# bq24259_BatteryCharger.net
KiCad netlist of a schematic drawn in Altium Designer
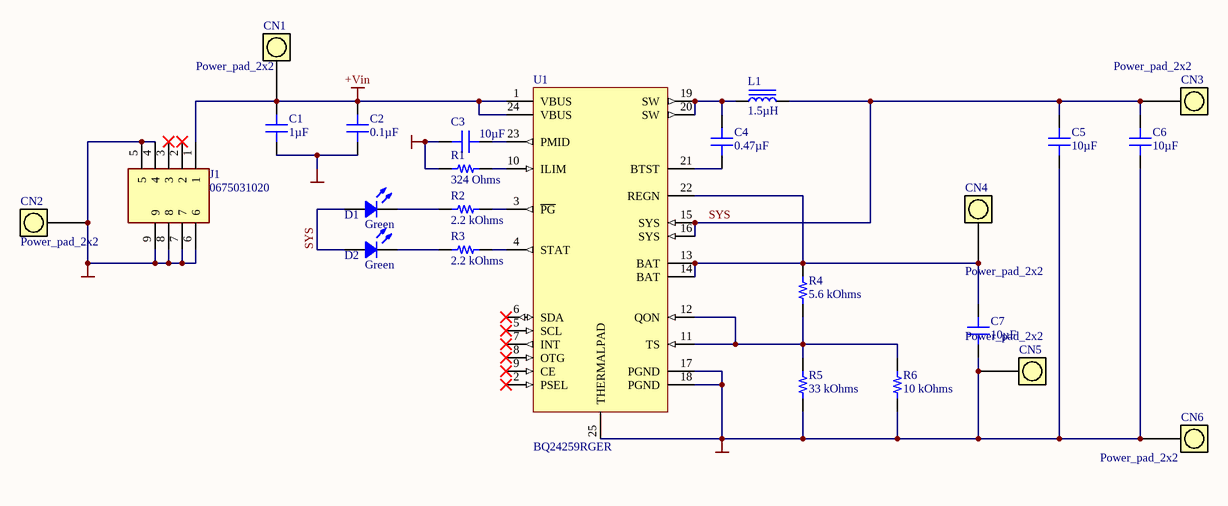
[diagram p0: bq24259_BatteryCharger.SchDoc]

(export (version "E")
  (design (tool "Eeschema 10.0.6"))
  (components
    (comp (ref "C1")
      (value "1µF")
      (footprint "CAP 0805_2012")
      (description "CAP CER 1UF 10V X7R 0805")
      (fields (field (name "PART NUMBER") "MM05ZC105KCZ2A") (field (name "MANUFACTURER") "AVX Corporation"))
      (libsource (lib "Celestial Altium Library - altium_library") (part "Capacitor"))
    )
    (comp (ref "C2")
      (value "0.1µF")
      (footprint "CAP 0805_2012")
      (description "CAP CER 0.1UF 50V X7R 0805")
      (fields (field (name "PART NUMBER") "CC0805MRX7R9BB104") (field (name "MANUFACTURER") "Yageo"))
      (libsource (lib "Celestial Altium Library - altium_library") (part "Capacitor"))
    )
    (comp (ref "C3")
      (value "10µF")
      (footprint "CAP 0805_2012")
      (description "CAP CER 10UF 6.3V X7R 0805")
      (fields (field (name "PART NUMBER") "C0805X106K9RACAUTO") (field (name "MANUFACTURER") "KEMET"))
      (libsource (lib "Celestial Altium Library - altium_library") (part "Capacitor"))
    )
    (comp (ref "C4")
      (value "0.47µF")
      (footprint "CAP 0805_2012")
      (description "CAP CER 0.47UF 50V X7R 0805")
      (fields (field (name "PART NUMBER") "C0805C474K5RACAUTO") (field (name "MANUFACTURER") "KEMET"))
      (libsource (lib "Celestial Altium Library - altium_library") (part "Capacitor"))
    )
    (comp (ref "C5")
      (value "10µF")
      (footprint "CAP 0805_2012")
      (description "CAP CER 10UF 6.3V X7R 0805")
      (fields (field (name "PART NUMBER") "C0805X106K9RACAUTO") (field (name "MANUFACTURER") "KEMET"))
      (libsource (lib "Celestial Altium Library - altium_library") (part "Capacitor"))
    )
    (comp (ref "C6")
      (value "10µF")
      (footprint "CAP 0805_2012")
      (description "CAP CER 10UF 6.3V X7R 0805")
      (fields (field (name "PART NUMBER") "C0805X106K9RACAUTO") (field (name "MANUFACTURER") "KEMET"))
      (libsource (lib "Celestial Altium Library - altium_library") (part "Capacitor"))
    )
    (comp (ref "C7")
      (value "10µF")
      (footprint "CAP 0805_2012")
      (description "CAP CER 10UF 6.3V X7R 0805")
      (fields (field (name "PART NUMBER") "C0805X106K9RACAUTO") (field (name "MANUFACTURER") "KEMET"))
      (libsource (lib "Celestial Altium Library - altium_library") (part "Capacitor"))
    )
    (comp (ref "CN1")
      (value "Power_pad_2x2")
      (footprint "Power_pad_2x2")
      (libsource (lib "") (part "Power_pad_2x2_2"))
    )
    (comp (ref "CN2")
      (value "Power_pad_2x2")
      (footprint "Power_pad_2x2")
      (libsource (lib "") (part "Power_pad_2x2_1"))
    )
    (comp (ref "CN3")
      (value "Power_pad_2x2")
      (footprint "Power_pad_2x2")
      (libsource (lib "AltiumLive") (part "Power_pad_2x2"))
    )
    (comp (ref "CN4")
      (value "Power_pad_2x2")
      (footprint "Power_pad_2x2")
      (libsource (lib "") (part "Power_pad_2x2_2"))
    )
    (comp (ref "CN5")
      (value "Power_pad_2x2")
      (footprint "Power_pad_2x2")
      (libsource (lib "AltiumLive") (part "Power_pad_2x2"))
    )
    (comp (ref "CN6")
      (value "Power_pad_2x2")
      (footprint "Power_pad_2x2")
      (libsource (lib "AltiumLive") (part "Power_pad_2x2"))
    )
    (comp (ref "D1")
      (value "Green")
      (footprint "LED 0603_1608 GREEN")
      (description "LED GREEN DIFFUSED 0603 SMD")
      (fields
        (field (name "PART NUMBER") "LG L29K-G2J1-24-Z")
        (field (name "MANUFACTURER") "OSRAM Opto Semiconductors Inc.")
      )
      (libsource (lib "Celestial Altium Library - altium_library") (part "LED"))
    )
    (comp (ref "D2")
      (value "Green")
      (footprint "LED 0603_1608 GREEN")
      (description "LED GREEN DIFFUSED 0603 SMD")
      (fields
        (field (name "PART NUMBER") "LG L29K-G2J1-24-Z")
        (field (name "MANUFACTURER") "OSRAM Opto Semiconductors Inc.")
      )
      (libsource (lib "Celestial Altium Library - altium_library") (part "LED"))
    )
    (comp (ref "J1")
      (value "0675031020")
      (footprint "SamacSys:0675031020")
      (description "Connector")
      (libsource (lib "AltiumLive") (part "0675031020"))
    )
    (comp (ref "L1")
      (value "1.5µH")
      (footprint "IND 1008_2520")
      (description "FIXED IND 1.5UH 1.5A 70 MOHM SMD")
      (fields (field (name "PART NUMBER") "ASMPH-1008-1R5M-T") (field (name "MANUFACTURER") "Abracon LLC"))
      (libsource (lib "Celestial Altium Library - altium_library") (part "Inductor"))
    )
    (comp (ref "R1")
      (value "324 Ohms")
      (footprint "RES 0805_2012")
      (description "RES SMD 324 OHM 1% 1/8W 0805")
      (fields (field (name "PART NUMBER") "RC0805FR-07324RL") (field (name "MANUFACTURER") "Yageo"))
      (libsource (lib "Celestial Altium Library - altium_library") (part "Resistor"))
    )
    (comp (ref "R2")
      (value "2.2 kOhms")
      (footprint "RES 0805_2012")
      (description "RES 2.2K OHM 0.1% 1/8W 0805")
      (fields
        (field (name "PART NUMBER") "ERA-6APB222V")
        (field (name "MANUFACTURER") "Panasonic Electronic Components")
      )
      (libsource (lib "Celestial Altium Library - altium_library") (part "Resistor"))
    )
    (comp (ref "R3")
      (value "2.2 kOhms")
      (footprint "RES 0805_2012")
      (description "RES 2.2K OHM 0.1% 1/8W 0805")
      (fields
        (field (name "PART NUMBER") "ERA-6APB222V")
        (field (name "MANUFACTURER") "Panasonic Electronic Components")
      )
      (libsource (lib "Celestial Altium Library - altium_library") (part "Resistor"))
    )
    (comp (ref "R4")
      (value "5.6 kOhms")
      (footprint "RES 0805_2012")
      (description "RES 5.6K OHM 0.1% 1/8W 0805")
      (fields (field (name "PART NUMBER") "AT0805BRD075K6L") (field (name "MANUFACTURER") "Yageo"))
      (libsource (lib "Celestial Altium Library - altium_library") (part "Resistor"))
    )
    (comp (ref "R5")
      (value "33 kOhms")
      (footprint "RES 0805_2012")
      (description "RES SMD 33K OHM 1% 1/8W 0805")
      (fields
        (field (name "PART NUMBER") "ERJ-6ENF3302V")
        (field (name "MANUFACTURER") "Panasonic Electronic Components")
      )
      (libsource (lib "Celestial Altium Library - altium_library") (part "Resistor"))
    )
    (comp (ref "R6")
      (value "10 kOhms")
      (footprint "RES 0805_2012")
      (description "RES SMD 10K OHM 1% 1/8W 0805")
      (fields (field (name "PART NUMBER") "CRCW080510K0FKEA") (field (name "MANUFACTURER") "Vishay Dale"))
      (libsource (lib "Celestial Altium Library - altium_library") (part "Resistor"))
    )
    (comp (ref "U1")
      (value "BQ24259RGER")
      (footprint "QFN50P400X400X100-25N")
      (description "IC BATTERY CHARGER 2A LION 24QFN")
      (fields (field (name "MANUFACTURER") "Texas Instruments"))
      (libsource (lib "AltiumLive") (part "BQ24259RGER"))
    )
  )
  (nets
    (net (code "1") (name "+Vin") (class "Default")
      (node (ref "C1") (pin "2") (pinfunction "2_2") (pintype "passive"))
      (node (ref "C2") (pin "2") (pinfunction "2_2") (pintype "passive"))
      (node (ref "CN1") (pin "1") (pinfunction "1_1") (pintype "passive"))
      (node (ref "J1") (pin "1") (pinfunction "1_1") (pintype "passive"))
      (node (ref "U1") (pin "1") (pinfunction "VBUS_1") (pintype "power_in"))
      (node (ref "U1") (pin "24") (pinfunction "VBUS_24") (pintype "power_in"))
    )
    (net (code "2") (name "/SYS") (class "Default")
      (node (ref "C5") (pin "2") (pinfunction "2_2") (pintype "passive"))
      (node (ref "C6") (pin "2") (pinfunction "2_2") (pintype "passive"))
      (node (ref "CN3") (pin "1") (pinfunction "1_1") (pintype "passive"))
      (node (ref "D1") (pin "1") (pinfunction "1_1") (pintype "passive"))
      (node (ref "D2") (pin "1") (pinfunction "1_1") (pintype "passive"))
      (node (ref "L1") (pin "2") (pinfunction "2_2") (pintype "passive"))
      (node (ref "U1") (pin "15") (pinfunction "SYS_15") (pintype "input"))
      (node (ref "U1") (pin "16") (pinfunction "SYS_16") (pintype "input"))
    )
    (net (code "3") (name "GND") (class "Default")
      (node (ref "C1") (pin "1") (pinfunction "1_1") (pintype "passive"))
      (node (ref "C2") (pin "1") (pinfunction "1_1") (pintype "passive"))
      (node (ref "C3") (pin "1") (pinfunction "1_1") (pintype "passive"))
      (node (ref "C5") (pin "1") (pinfunction "1_1") (pintype "passive"))
      (node (ref "C6") (pin "1") (pinfunction "1_1") (pintype "passive"))
      (node (ref "C7") (pin "1") (pinfunction "1_1") (pintype "passive"))
      (node (ref "CN2") (pin "1") (pinfunction "1_1") (pintype "passive"))
      (node (ref "CN5") (pin "1") (pinfunction "1_1") (pintype "passive"))
      (node (ref "CN6") (pin "1") (pinfunction "1_1") (pintype "passive"))
      (node (ref "J1") (pin "4") (pinfunction "4_4") (pintype "passive"))
      (node (ref "J1") (pin "5") (pinfunction "5_5") (pintype "passive"))
      (node (ref "J1") (pin "6") (pinfunction "6_6") (pintype "passive"))
      (node (ref "J1") (pin "7") (pinfunction "7_7") (pintype "passive"))
      (node (ref "J1") (pin "8") (pinfunction "8_8") (pintype "passive"))
      (node (ref "J1") (pin "9") (pinfunction "9_9") (pintype "passive"))
      (node (ref "R1") (pin "1") (pinfunction "1_1") (pintype "passive"))
      (node (ref "R5") (pin "1") (pinfunction "1_1") (pintype "passive"))
      (node (ref "R6") (pin "1") (pinfunction "1_1") (pintype "passive"))
      (node (ref "U1") (pin "17") (pinfunction "PGND_17") (pintype "power_in"))
      (node (ref "U1") (pin "18") (pinfunction "PGND_18") (pintype "power_in"))
      (node (ref "U1") (pin "25") (pinfunction "THERMALPAD_25") (pintype "power_in"))
    )
    (net (code "4") (name "Net-(C4-Pad2)") (class "Default")
      (node (ref "C4") (pin "2") (pinfunction "2_2") (pintype "passive"))
      (node (ref "L1") (pin "1") (pinfunction "1_1") (pintype "passive"))
      (node (ref "U1") (pin "19") (pinfunction "SW_19") (pintype "output"))
      (node (ref "U1") (pin "20") (pinfunction "SW_20") (pintype "output"))
    )
    (net (code "5") (name "Net-(D1-Pad2)") (class "Default")
      (node (ref "D1") (pin "2") (pinfunction "2_2") (pintype "passive"))
      (node (ref "R2") (pin "1") (pinfunction "1_1") (pintype "passive"))
    )
    (net (code "6") (name "Net-(D2-Pad2)") (class "Default")
      (node (ref "D2") (pin "2") (pinfunction "2_2") (pintype "passive"))
      (node (ref "R3") (pin "1") (pinfunction "1_1") (pintype "passive"))
    )
    (net (code "7") (name "Net-(U1-BTST)") (class "Default")
      (node (ref "C4") (pin "1") (pinfunction "1_1") (pintype "passive"))
      (node (ref "U1") (pin "21") (pinfunction "BTST_21") (pintype "power_in"))
    )
    (net (code "8") (name "Net-(U1-ILIM)") (class "Default")
      (node (ref "R1") (pin "2") (pinfunction "2_2") (pintype "passive"))
      (node (ref "U1") (pin "10") (pinfunction "ILIM_10") (pintype "input"))
    )
    (net (code "9") (name "Net-(U1-PMID)") (class "Default")
      (node (ref "C3") (pin "2") (pinfunction "2_2") (pintype "passive"))
      (node (ref "U1") (pin "23") (pinfunction "PMID_23") (pintype "output"))
    )
    (net (code "10") (name "Net-(U1-QON)") (class "Default")
      (node (ref "R4") (pin "2") (pinfunction "2_2") (pintype "passive"))
      (node (ref "R5") (pin "2") (pinfunction "2_2") (pintype "passive"))
      (node (ref "R6") (pin "2") (pinfunction "2_2") (pintype "passive"))
      (node (ref "U1") (pin "11") (pinfunction "TS_11") (pintype "input"))
      (node (ref "U1") (pin "12") (pinfunction "QON_12") (pintype "input"))
    )
    (net (code "11") (name "Net-(U1-REGN)") (class "Default")
      (node (ref "C7") (pin "2") (pinfunction "2_2") (pintype "passive"))
      (node (ref "CN4") (pin "1") (pinfunction "1_1") (pintype "passive"))
      (node (ref "R4") (pin "1") (pinfunction "1_1") (pintype "passive"))
      (node (ref "U1") (pin "13") (pinfunction "BAT_13") (pintype "power_in"))
      (node (ref "U1") (pin "14") (pinfunction "BAT_14") (pintype "power_in"))
      (node (ref "U1") (pin "22") (pinfunction "REGN_22") (pintype "power_in"))
    )
    (net (code "12") (name "Net-(U1-STAT)") (class "Default")
      (node (ref "R3") (pin "2") (pinfunction "2_2") (pintype "passive"))
      (node (ref "U1") (pin "4") (pinfunction "STAT_4") (pintype "output"))
    )
    (net (code "13") (name "Net-(U1-~{PG})") (class "Default")
      (node (ref "R2") (pin "2") (pinfunction "2_2") (pintype "passive"))
      (node (ref "U1") (pin "3") (pinfunction "~{PG}_3") (pintype "output"))
    )
    (net (code "14") (name "unconnected-(J1-Pad2)") (class "Default")
      (node (ref "J1") (pin "2") (pinfunction "2_2") (pintype "passive+no_connect"))
    )
    (net (code "15") (name "unconnected-(J1-Pad3)") (class "Default")
      (node (ref "J1") (pin "3") (pinfunction "3_3") (pintype "passive+no_connect"))
    )
    (net (code "16") (name "unconnected-(U1-CE-Pad9)") (class "Default")
      (node (ref "U1") (pin "9") (pinfunction "CE_9") (pintype "input+no_connect"))
    )
    (net (code "17") (name "unconnected-(U1-INT-Pad7)") (class "Default")
      (node (ref "U1") (pin "7") (pinfunction "INT_7") (pintype "output+no_connect"))
    )
    (net (code "18") (name "unconnected-(U1-OTG-Pad8)") (class "Default")
      (node (ref "U1") (pin "8") (pinfunction "OTG_8") (pintype "input+no_connect"))
    )
    (net (code "19") (name "unconnected-(U1-PSEL-Pad2)") (class "Default")
      (node (ref "U1") (pin "2") (pinfunction "PSEL_2") (pintype "input+no_connect"))
    )
    (net (code "20") (name "unconnected-(U1-SCL-Pad5)") (class "Default")
      (node (ref "U1") (pin "5") (pinfunction "SCL_5") (pintype "input+no_connect"))
    )
    (net (code "21") (name "unconnected-(U1-SDA-Pad6)") (class "Default")
      (node (ref "U1") (pin "6") (pinfunction "SDA_6") (pintype "bidirectional+no_connect"))
    )
  )
)
